# Diff_AMP_Inputs.net
KiCad netlist of a schematic drawn in Altium Designer
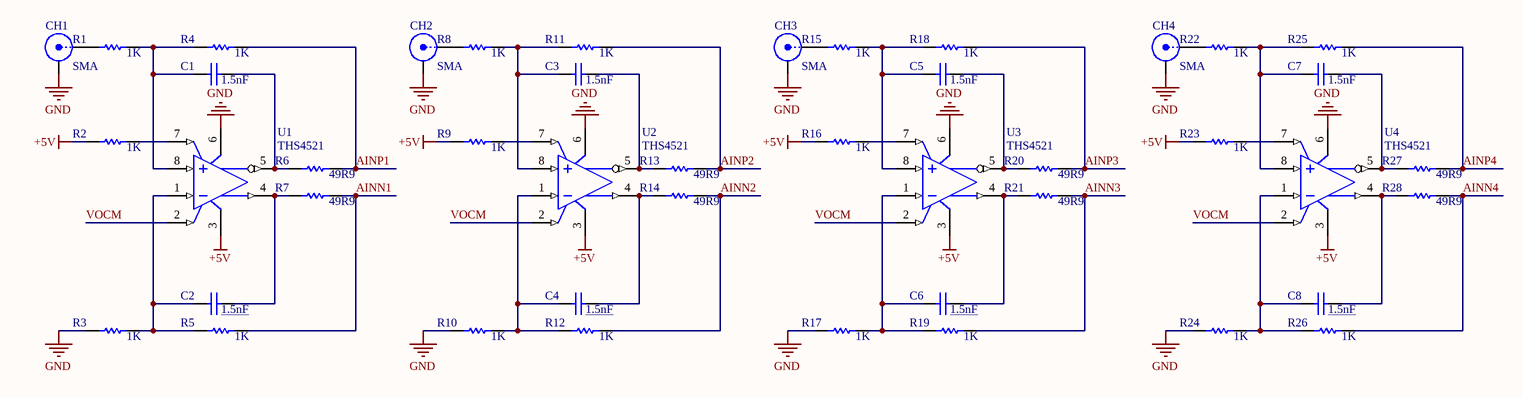
[diagram p0: Diff AMP Inputs.SchDoc]

(export (version "E")
  (design (tool "Eeschema 10.0.6"))
  (components
    (comp (ref "C1")
      (value "1.5nF")
      (footprint "CAPC0603(1608)55_M")
      (libsource (lib "Slivy's ibrary") (part "CAP"))
    )
    (comp (ref "C2")
      (value "1.5nF")
      (footprint "CAPC0603(1608)55_M")
      (libsource (lib "Slivy's ibrary") (part "CAP"))
    )
    (comp (ref "C3")
      (value "1.5nF")
      (footprint "CAPC0603(1608)55_M")
      (libsource (lib "Slivy's ibrary") (part "CAP"))
    )
    (comp (ref "C4")
      (value "1.5nF")
      (footprint "CAPC0603(1608)55_M")
      (libsource (lib "Slivy's ibrary") (part "CAP"))
    )
    (comp (ref "C5")
      (value "1.5nF")
      (footprint "CAPC0603(1608)55_M")
      (libsource (lib "Slivy's ibrary") (part "CAP"))
    )
    (comp (ref "C6")
      (value "1.5nF")
      (footprint "CAPC0603(1608)55_M")
      (libsource (lib "Slivy's ibrary") (part "CAP"))
    )
    (comp (ref "C7")
      (value "1.5nF")
      (footprint "CAPC0603(1608)55_M")
      (libsource (lib "Slivy's ibrary") (part "CAP"))
    )
    (comp (ref "C8")
      (value "1.5nF")
      (footprint "CAPC0603(1608)55_M")
      (libsource (lib "Slivy's ibrary") (part "CAP"))
    )
    (comp (ref "CH1")
      (value "SMA")
      (footprint "SMA-V")
      (fields (field (name "PUBLISHER") "Altium Limited"))
      (libsource (lib "Slivy's ibrary") (part "SMA"))
    )
    (comp (ref "CH2")
      (value "SMA")
      (footprint "SMA-V")
      (fields (field (name "PUBLISHER") "Altium Limited"))
      (libsource (lib "Slivy's ibrary") (part "SMA"))
    )
    (comp (ref "CH3")
      (value "SMA")
      (footprint "SMA-V")
      (fields (field (name "PUBLISHER") "Altium Limited"))
      (libsource (lib "Slivy's ibrary") (part "SMA"))
    )
    (comp (ref "CH4")
      (value "SMA")
      (footprint "SMA-V")
      (fields (field (name "PUBLISHER") "Altium Limited"))
      (libsource (lib "Slivy's ibrary") (part "SMA"))
    )
    (comp (ref "R1")
      (value "1K")
      (footprint "RESC0603(1608)_M")
      (libsource (lib "Slivy's ibrary") (part "RES"))
    )
    (comp (ref "R2")
      (value "1K")
      (footprint "RESC0603(1608)_M")
      (libsource (lib "Slivy's ibrary") (part "RES"))
    )
    (comp (ref "R3")
      (value "1K")
      (footprint "RESC0603(1608)_M")
      (libsource (lib "Slivy's ibrary") (part "RES"))
    )
    (comp (ref "R4")
      (value "1K")
      (footprint "RESC0603(1608)_M")
      (libsource (lib "Slivy's ibrary") (part "RES"))
    )
    (comp (ref "R5")
      (value "1K")
      (footprint "RESC0603(1608)_M")
      (libsource (lib "Slivy's ibrary") (part "RES"))
    )
    (comp (ref "R6")
      (value "49R9")
      (footprint "RESC0603(1608)_M")
      (libsource (lib "Slivy's ibrary") (part "RES"))
    )
    (comp (ref "R7")
      (value "49R9")
      (footprint "RESC0603(1608)_M")
      (libsource (lib "Slivy's ibrary") (part "RES"))
    )
    (comp (ref "R8")
      (value "1K")
      (footprint "RESC0603(1608)_M")
      (libsource (lib "Slivy's ibrary") (part "RES"))
    )
    (comp (ref "R9")
      (value "1K")
      (footprint "RESC0603(1608)_M")
      (libsource (lib "Slivy's ibrary") (part "RES"))
    )
    (comp (ref "R10")
      (value "1K")
      (footprint "RESC0603(1608)_M")
      (libsource (lib "Slivy's ibrary") (part "RES"))
    )
    (comp (ref "R11")
      (value "1K")
      (footprint "RESC0603(1608)_M")
      (libsource (lib "Slivy's ibrary") (part "RES"))
    )
    (comp (ref "R12")
      (value "1K")
      (footprint "RESC0603(1608)_M")
      (libsource (lib "Slivy's ibrary") (part "RES"))
    )
    (comp (ref "R13")
      (value "49R9")
      (footprint "RESC0603(1608)_M")
      (libsource (lib "Slivy's ibrary") (part "RES"))
    )
    (comp (ref "R14")
      (value "49R9")
      (footprint "RESC0603(1608)_M")
      (libsource (lib "Slivy's ibrary") (part "RES"))
    )
    (comp (ref "R15")
      (value "1K")
      (footprint "RESC0603(1608)_M")
      (libsource (lib "Slivy's ibrary") (part "RES"))
    )
    (comp (ref "R16")
      (value "1K")
      (footprint "RESC0603(1608)_M")
      (libsource (lib "Slivy's ibrary") (part "RES"))
    )
    (comp (ref "R17")
      (value "1K")
      (footprint "RESC0603(1608)_M")
      (libsource (lib "Slivy's ibrary") (part "RES"))
    )
    (comp (ref "R18")
      (value "1K")
      (footprint "RESC0603(1608)_M")
      (libsource (lib "Slivy's ibrary") (part "RES"))
    )
    (comp (ref "R19")
      (value "1K")
      (footprint "RESC0603(1608)_M")
      (libsource (lib "Slivy's ibrary") (part "RES"))
    )
    (comp (ref "R20")
      (value "49R9")
      (footprint "RESC0603(1608)_M")
      (libsource (lib "Slivy's ibrary") (part "RES"))
    )
    (comp (ref "R21")
      (value "49R9")
      (footprint "RESC0603(1608)_M")
      (libsource (lib "Slivy's ibrary") (part "RES"))
    )
    (comp (ref "R22")
      (value "1K")
      (footprint "RESC0603(1608)_M")
      (libsource (lib "Slivy's ibrary") (part "RES"))
    )
    (comp (ref "R23")
      (value "1K")
      (footprint "RESC0603(1608)_M")
      (libsource (lib "Slivy's ibrary") (part "RES"))
    )
    (comp (ref "R24")
      (value "1K")
      (footprint "RESC0603(1608)_M")
      (libsource (lib "Slivy's ibrary") (part "RES"))
    )
    (comp (ref "R25")
      (value "1K")
      (footprint "RESC0603(1608)_M")
      (libsource (lib "Slivy's ibrary") (part "RES"))
    )
    (comp (ref "R26")
      (value "1K")
      (footprint "RESC0603(1608)_M")
      (libsource (lib "Slivy's ibrary") (part "RES"))
    )
    (comp (ref "R27")
      (value "49R9")
      (footprint "RESC0603(1608)_M")
      (libsource (lib "Slivy's ibrary") (part "RES"))
    )
    (comp (ref "R28")
      (value "49R9")
      (footprint "RESC0603(1608)_M")
      (libsource (lib "Slivy's ibrary") (part "RES"))
    )
    (comp (ref "U1")
      (value "THS4521")
      (footprint "SOIC8")
      (libsource (lib "Slivy's ibrary") (part "THS4521"))
    )
    (comp (ref "U2")
      (value "THS4521")
      (footprint "SOIC8")
      (libsource (lib "Slivy's ibrary") (part "THS4521"))
    )
    (comp (ref "U3")
      (value "THS4521")
      (footprint "SOIC8")
      (libsource (lib "Slivy's ibrary") (part "THS4521"))
    )
    (comp (ref "U4")
      (value "THS4521")
      (footprint "SOIC8")
      (libsource (lib "Slivy's ibrary") (part "THS4521"))
    )
  )
  (nets
    (net (code "1") (name "+5V") (class "Default")
      (node (ref "R16") (pin "1") (pinfunction "1_1") (pintype "passive"))
      (node (ref "R2") (pin "1") (pinfunction "1_1") (pintype "passive"))
      (node (ref "R23") (pin "1") (pinfunction "1_1") (pintype "passive"))
      (node (ref "R9") (pin "1") (pinfunction "1_1") (pintype "passive"))
      (node (ref "U1") (pin "3") (pinfunction "VS+_3") (pintype "power_in"))
      (node (ref "U2") (pin "3") (pinfunction "VS+_3") (pintype "power_in"))
      (node (ref "U3") (pin "3") (pinfunction "VS+_3") (pintype "power_in"))
      (node (ref "U4") (pin "3") (pinfunction "VS+_3") (pintype "power_in"))
    )
    (net (code "2") (name "/AINN1") (class "Default")
      (node (ref "R5") (pin "2") (pinfunction "2_2") (pintype "passive"))
      (node (ref "R7") (pin "2") (pinfunction "2_2") (pintype "passive"))
    )
    (net (code "3") (name "/AINN2") (class "Default")
      (node (ref "R12") (pin "2") (pinfunction "2_2") (pintype "passive"))
      (node (ref "R14") (pin "2") (pinfunction "2_2") (pintype "passive"))
    )
    (net (code "4") (name "/AINN3") (class "Default")
      (node (ref "R19") (pin "2") (pinfunction "2_2") (pintype "passive"))
      (node (ref "R21") (pin "2") (pinfunction "2_2") (pintype "passive"))
    )
    (net (code "5") (name "/AINN4") (class "Default")
      (node (ref "R26") (pin "2") (pinfunction "2_2") (pintype "passive"))
      (node (ref "R28") (pin "2") (pinfunction "2_2") (pintype "passive"))
    )
    (net (code "6") (name "/AINP1") (class "Default")
      (node (ref "R4") (pin "2") (pinfunction "2_2") (pintype "passive"))
      (node (ref "R6") (pin "2") (pinfunction "2_2") (pintype "passive"))
    )
    (net (code "7") (name "/AINP2") (class "Default")
      (node (ref "R11") (pin "2") (pinfunction "2_2") (pintype "passive"))
      (node (ref "R13") (pin "2") (pinfunction "2_2") (pintype "passive"))
    )
    (net (code "8") (name "/AINP3") (class "Default")
      (node (ref "R18") (pin "2") (pinfunction "2_2") (pintype "passive"))
      (node (ref "R20") (pin "2") (pinfunction "2_2") (pintype "passive"))
    )
    (net (code "9") (name "/AINP4") (class "Default")
      (node (ref "R25") (pin "2") (pinfunction "2_2") (pintype "passive"))
      (node (ref "R27") (pin "2") (pinfunction "2_2") (pintype "passive"))
    )
    (net (code "10") (name "/VOCM") (class "Default")
      (node (ref "U1") (pin "2") (pinfunction "VOCM_2") (pintype "input"))
      (node (ref "U2") (pin "2") (pinfunction "VOCM_2") (pintype "input"))
      (node (ref "U3") (pin "2") (pinfunction "VOCM_2") (pintype "input"))
      (node (ref "U4") (pin "2") (pinfunction "VOCM_2") (pintype "input"))
    )
    (net (code "11") (name "GND") (class "Default")
      (node (ref "CH1") (pin "2") (pinfunction "Y_2") (pintype "passive"))
      (node (ref "CH2") (pin "2") (pinfunction "Y_2") (pintype "passive"))
      (node (ref "CH3") (pin "2") (pinfunction "Y_2") (pintype "passive"))
      (node (ref "CH4") (pin "2") (pinfunction "Y_2") (pintype "passive"))
      (node (ref "R10") (pin "1") (pinfunction "1_1") (pintype "passive"))
      (node (ref "R17") (pin "1") (pinfunction "1_1") (pintype "passive"))
      (node (ref "R24") (pin "1") (pinfunction "1_1") (pintype "passive"))
      (node (ref "R3") (pin "1") (pinfunction "1_1") (pintype "passive"))
      (node (ref "U1") (pin "6") (pinfunction "VS-_6") (pintype "power_in"))
      (node (ref "U2") (pin "6") (pinfunction "VS-_6") (pintype "power_in"))
      (node (ref "U3") (pin "6") (pinfunction "VS-_6") (pintype "power_in"))
      (node (ref "U4") (pin "6") (pinfunction "VS-_6") (pintype "power_in"))
    )
    (net (code "12") (name "Net-(CH1-X)") (class "Default")
      (node (ref "CH1") (pin "1") (pinfunction "X_1") (pintype "passive"))
      (node (ref "R1") (pin "1") (pinfunction "1_1") (pintype "passive"))
    )
    (net (code "13") (name "Net-(CH2-X)") (class "Default")
      (node (ref "CH2") (pin "1") (pinfunction "X_1") (pintype "passive"))
      (node (ref "R8") (pin "1") (pinfunction "1_1") (pintype "passive"))
    )
    (net (code "14") (name "Net-(CH3-X)") (class "Default")
      (node (ref "CH3") (pin "1") (pinfunction "X_1") (pintype "passive"))
      (node (ref "R15") (pin "1") (pinfunction "1_1") (pintype "passive"))
    )
    (net (code "15") (name "Net-(CH4-X)") (class "Default")
      (node (ref "CH4") (pin "1") (pinfunction "X_1") (pintype "passive"))
      (node (ref "R22") (pin "1") (pinfunction "1_1") (pintype "passive"))
    )
    (net (code "16") (name "Net-(U1-VIN+)") (class "Default")
      (node (ref "C1") (pin "1") (pinfunction "1_1") (pintype "passive"))
      (node (ref "R1") (pin "2") (pinfunction "2_2") (pintype "passive"))
      (node (ref "R4") (pin "1") (pinfunction "1_1") (pintype "passive"))
      (node (ref "U1") (pin "8") (pinfunction "VIN+_8") (pintype "input"))
    )
    (net (code "17") (name "Net-(U1-VIN-)") (class "Default")
      (node (ref "C2") (pin "1") (pinfunction "1_1") (pintype "passive"))
      (node (ref "R3") (pin "2") (pinfunction "2_2") (pintype "passive"))
      (node (ref "R5") (pin "1") (pinfunction "1_1") (pintype "passive"))
      (node (ref "U1") (pin "1") (pinfunction "VIN-_1") (pintype "input"))
    )
    (net (code "18") (name "Net-(U1-VOUT+)") (class "Default")
      (node (ref "C2") (pin "2") (pinfunction "2_2") (pintype "passive"))
      (node (ref "R7") (pin "1") (pinfunction "1_1") (pintype "passive"))
      (node (ref "U1") (pin "4") (pinfunction "VOUT+_4") (pintype "output"))
    )
    (net (code "19") (name "Net-(U1-VOUT-)") (class "Default")
      (node (ref "C1") (pin "2") (pinfunction "2_2") (pintype "passive"))
      (node (ref "R6") (pin "1") (pinfunction "1_1") (pintype "passive"))
      (node (ref "U1") (pin "5") (pinfunction "VOUT-_5") (pintype "output"))
    )
    (net (code "20") (name "Net-(U1-~{PD})") (class "Default")
      (node (ref "R2") (pin "2") (pinfunction "2_2") (pintype "passive"))
      (node (ref "U1") (pin "7") (pinfunction "~{PD}_7") (pintype "input"))
    )
    (net (code "21") (name "Net-(U2-VIN+)") (class "Default")
      (node (ref "C3") (pin "1") (pinfunction "1_1") (pintype "passive"))
      (node (ref "R11") (pin "1") (pinfunction "1_1") (pintype "passive"))
      (node (ref "R8") (pin "2") (pinfunction "2_2") (pintype "passive"))
      (node (ref "U2") (pin "8") (pinfunction "VIN+_8") (pintype "input"))
    )
    (net (code "22") (name "Net-(U2-VIN-)") (class "Default")
      (node (ref "C4") (pin "1") (pinfunction "1_1") (pintype "passive"))
      (node (ref "R10") (pin "2") (pinfunction "2_2") (pintype "passive"))
      (node (ref "R12") (pin "1") (pinfunction "1_1") (pintype "passive"))
      (node (ref "U2") (pin "1") (pinfunction "VIN-_1") (pintype "input"))
    )
    (net (code "23") (name "Net-(U2-VOUT+)") (class "Default")
      (node (ref "C4") (pin "2") (pinfunction "2_2") (pintype "passive"))
      (node (ref "R14") (pin "1") (pinfunction "1_1") (pintype "passive"))
      (node (ref "U2") (pin "4") (pinfunction "VOUT+_4") (pintype "output"))
    )
    (net (code "24") (name "Net-(U2-VOUT-)") (class "Default")
      (node (ref "C3") (pin "2") (pinfunction "2_2") (pintype "passive"))
      (node (ref "R13") (pin "1") (pinfunction "1_1") (pintype "passive"))
      (node (ref "U2") (pin "5") (pinfunction "VOUT-_5") (pintype "output"))
    )
    (net (code "25") (name "Net-(U2-~{PD})") (class "Default")
      (node (ref "R9") (pin "2") (pinfunction "2_2") (pintype "passive"))
      (node (ref "U2") (pin "7") (pinfunction "~{PD}_7") (pintype "input"))
    )
    (net (code "26") (name "Net-(U3-VIN+)") (class "Default")
      (node (ref "C5") (pin "1") (pinfunction "1_1") (pintype "passive"))
      (node (ref "R15") (pin "2") (pinfunction "2_2") (pintype "passive"))
      (node (ref "R18") (pin "1") (pinfunction "1_1") (pintype "passive"))
      (node (ref "U3") (pin "8") (pinfunction "VIN+_8") (pintype "input"))
    )
    (net (code "27") (name "Net-(U3-VIN-)") (class "Default")
      (node (ref "C6") (pin "1") (pinfunction "1_1") (pintype "passive"))
      (node (ref "R17") (pin "2") (pinfunction "2_2") (pintype "passive"))
      (node (ref "R19") (pin "1") (pinfunction "1_1") (pintype "passive"))
      (node (ref "U3") (pin "1") (pinfunction "VIN-_1") (pintype "input"))
    )
    (net (code "28") (name "Net-(U3-VOUT+)") (class "Default")
      (node (ref "C6") (pin "2") (pinfunction "2_2") (pintype "passive"))
      (node (ref "R21") (pin "1") (pinfunction "1_1") (pintype "passive"))
      (node (ref "U3") (pin "4") (pinfunction "VOUT+_4") (pintype "output"))
    )
    (net (code "29") (name "Net-(U3-VOUT-)") (class "Default")
      (node (ref "C5") (pin "2") (pinfunction "2_2") (pintype "passive"))
      (node (ref "R20") (pin "1") (pinfunction "1_1") (pintype "passive"))
      (node (ref "U3") (pin "5") (pinfunction "VOUT-_5") (pintype "output"))
    )
    (net (code "30") (name "Net-(U3-~{PD})") (class "Default")
      (node (ref "R16") (pin "2") (pinfunction "2_2") (pintype "passive"))
      (node (ref "U3") (pin "7") (pinfunction "~{PD}_7") (pintype "input"))
    )
    (net (code "31") (name "Net-(U4-VIN+)") (class "Default")
      (node (ref "C7") (pin "1") (pinfunction "1_1") (pintype "passive"))
      (node (ref "R22") (pin "2") (pinfunction "2_2") (pintype "passive"))
      (node (ref "R25") (pin "1") (pinfunction "1_1") (pintype "passive"))
      (node (ref "U4") (pin "8") (pinfunction "VIN+_8") (pintype "input"))
    )
    (net (code "32") (name "Net-(U4-VIN-)") (class "Default")
      (node (ref "C8") (pin "1") (pinfunction "1_1") (pintype "passive"))
      (node (ref "R24") (pin "2") (pinfunction "2_2") (pintype "passive"))
      (node (ref "R26") (pin "1") (pinfunction "1_1") (pintype "passive"))
      (node (ref "U4") (pin "1") (pinfunction "VIN-_1") (pintype "input"))
    )
    (net (code "33") (name "Net-(U4-VOUT+)") (class "Default")
      (node (ref "C8") (pin "2") (pinfunction "2_2") (pintype "passive"))
      (node (ref "R28") (pin "1") (pinfunction "1_1") (pintype "passive"))
      (node (ref "U4") (pin "4") (pinfunction "VOUT+_4") (pintype "output"))
    )
    (net (code "34") (name "Net-(U4-VOUT-)") (class "Default")
      (node (ref "C7") (pin "2") (pinfunction "2_2") (pintype "passive"))
      (node (ref "R27") (pin "1") (pinfunction "1_1") (pintype "passive"))
      (node (ref "U4") (pin "5") (pinfunction "VOUT-_5") (pintype "output"))
    )
    (net (code "35") (name "Net-(U4-~{PD})") (class "Default")
      (node (ref "R23") (pin "2") (pinfunction "2_2") (pintype "passive"))
      (node (ref "U4") (pin "7") (pinfunction "~{PD}_7") (pintype "input"))
    )
  )
)
